# Backplane.net
KiCad netlist of a schematic drawn in EAGLE
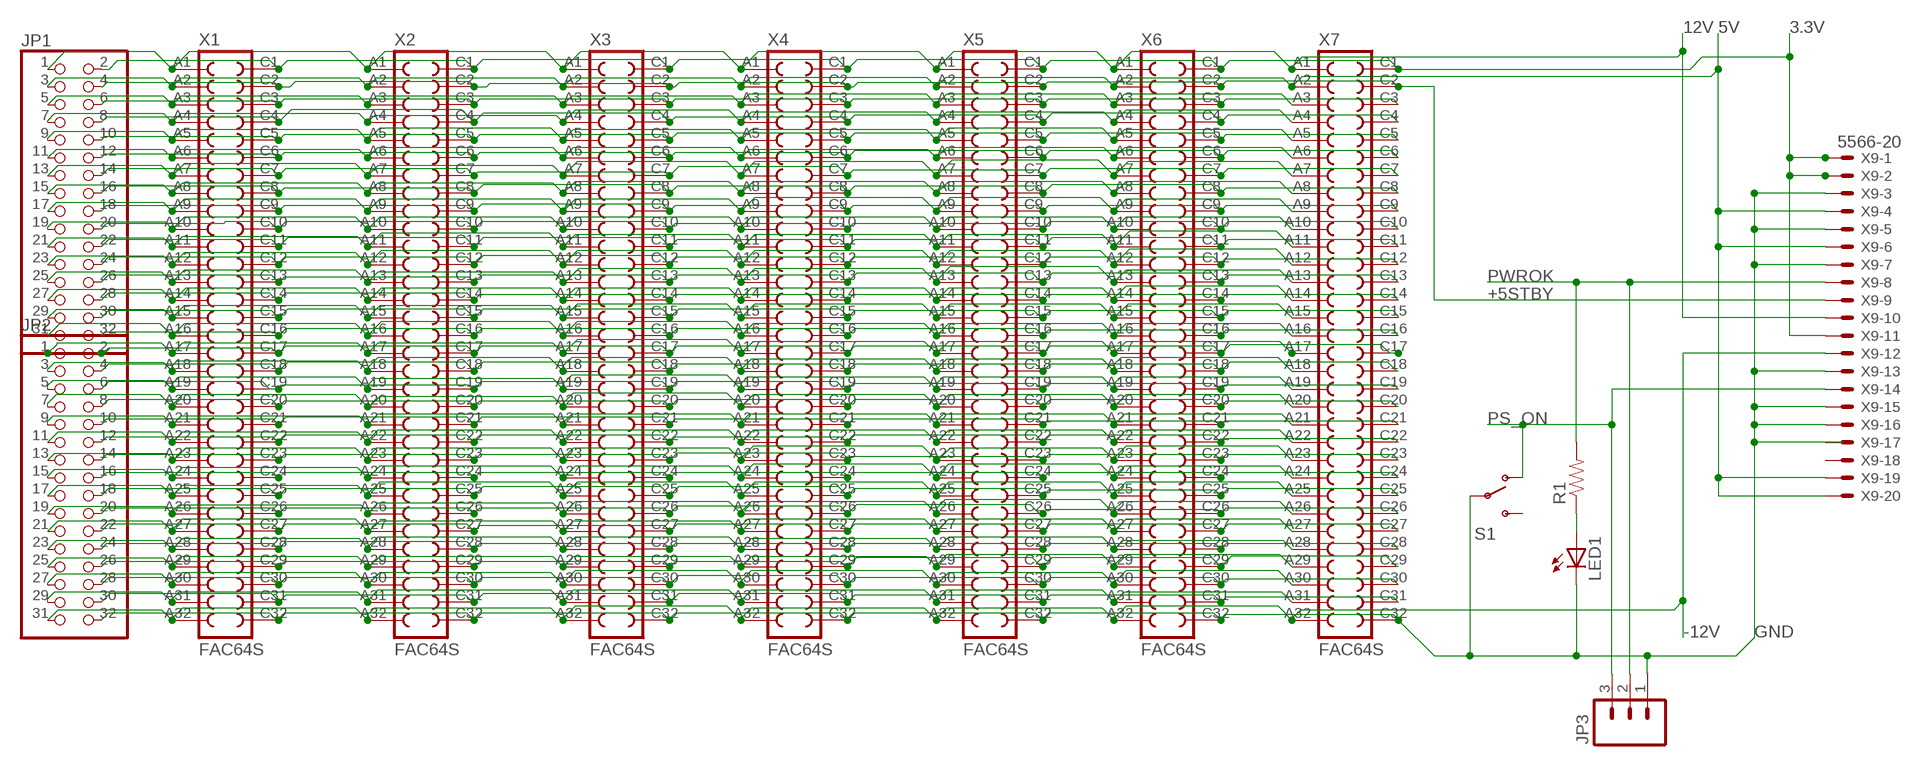
[diagram p0: schematic, sheet 1]

(export (version "E")
  (design (tool "Eeschema 10.0.6"))
  (components
    (comp (ref "JP1")
      (value "PINHD-2X16")
      (footprint "eagle-import:2X16")
      (libsource (lib "eagle-import") (part "PINHD-2X16"))
    )
    (comp (ref "JP2")
      (value "PINHD-2X16")
      (footprint "eagle-import:2X16")
      (libsource (lib "eagle-import") (part "PINHD-2X16"))
    )
    (comp (ref "JP3")
      (value "M03LONGPADS")
      (footprint "eagle-import:1X03_LONGPADS")
      (libsource (lib "eagle-import") (part "M03LONGPADS"))
    )
    (comp (ref "LED1")
      (value "LED3MM")
      (footprint "eagle-import:LED3MM")
      (libsource (lib "eagle-import") (part "LED3MM"))
    )
    (comp (ref "R1")
      (value "RESISTORKIT")
      (footprint "eagle-import:AXIAL-0.3-KIT")
      (libsource (lib "eagle-import") (part "RESISTORKIT"))
    )
    (comp (ref "S1")
      (value "SWITCH-SPDTPTH")
      (footprint "eagle-import:SWITCH-SPDT")
      (libsource (lib "eagle-import") (part "SWITCH-SPDTPTH"))
    )
    (comp (ref "X1")
      (value "FAC64S")
      (footprint "eagle-import:FAC64S")
      (libsource (lib "eagle-import") (part "FAC64S"))
    )
    (comp (ref "X2")
      (value "FAC64S")
      (footprint "eagle-import:FAC64S")
      (libsource (lib "eagle-import") (part "FAC64S"))
    )
    (comp (ref "X3")
      (value "FAC64S")
      (footprint "eagle-import:FAC64S")
      (libsource (lib "eagle-import") (part "FAC64S"))
    )
    (comp (ref "X4")
      (value "FAC64S")
      (footprint "eagle-import:FAC64S")
      (libsource (lib "eagle-import") (part "FAC64S"))
    )
    (comp (ref "X5")
      (value "FAC64S")
      (footprint "eagle-import:FAC64S")
      (libsource (lib "eagle-import") (part "FAC64S"))
    )
    (comp (ref "X6")
      (value "FAC64S")
      (footprint "eagle-import:FAC64S")
      (libsource (lib "eagle-import") (part "FAC64S"))
    )
    (comp (ref "X7")
      (value "FAC64S")
      (footprint "eagle-import:FAC64S")
      (libsource (lib "eagle-import") (part "FAC64S"))
    )
    (comp (ref "X9")
      (value "5566-20")
      (footprint "eagle-import:5566-20")
      (libsource (lib "eagle-import") (part "5566-20"))
    )
  )
  (nets
    (net (code "1") (name "/+5STBY") (class "Default")
      (node (ref "JP1") (pin "4") (pinfunction "4_4") (pintype "passive"))
      (node (ref "X1") (pin "C2") (pinfunction "C2_C2") (pintype "passive"))
      (node (ref "X2") (pin "C2") (pinfunction "C2_C2") (pintype "passive"))
      (node (ref "X3") (pin "C2") (pinfunction "C2_C2") (pintype "passive"))
      (node (ref "X4") (pin "C2") (pinfunction "C2_C2") (pintype "passive"))
      (node (ref "X5") (pin "C2") (pinfunction "C2_C2") (pintype "passive"))
      (node (ref "X6") (pin "C2") (pinfunction "C2_C2") (pintype "passive"))
      (node (ref "X7") (pin "C2") (pinfunction "C2_C2") (pintype "passive"))
      (node (ref "X9") (pin "9") (pinfunction "S_9") (pintype "passive"))
    )
    (net (code "2") (name "/-12V") (class "Default")
      (node (ref "JP2") (pin "31") (pinfunction "31_31") (pintype "passive"))
      (node (ref "X1") (pin "A32") (pinfunction "A32_A32") (pintype "passive"))
      (node (ref "X2") (pin "A32") (pinfunction "A32_A32") (pintype "passive"))
      (node (ref "X3") (pin "A32") (pinfunction "A32_A32") (pintype "passive"))
      (node (ref "X4") (pin "A32") (pinfunction "A32_A32") (pintype "passive"))
      (node (ref "X5") (pin "A32") (pinfunction "A32_A32") (pintype "passive"))
      (node (ref "X6") (pin "A32") (pinfunction "A32_A32") (pintype "passive"))
      (node (ref "X7") (pin "A32") (pinfunction "A32_A32") (pintype "passive"))
      (node (ref "X9") (pin "12") (pinfunction "S_12") (pintype "passive"))
    )
    (net (code "3") (name "/3.3V") (class "Default")
      (node (ref "JP1") (pin "2") (pinfunction "2_2") (pintype "passive"))
      (node (ref "X1") (pin "C1") (pinfunction "C1_C1") (pintype "passive"))
      (node (ref "X2") (pin "C1") (pinfunction "C1_C1") (pintype "passive"))
      (node (ref "X3") (pin "C1") (pinfunction "C1_C1") (pintype "passive"))
      (node (ref "X4") (pin "C1") (pinfunction "C1_C1") (pintype "passive"))
      (node (ref "X5") (pin "C1") (pinfunction "C1_C1") (pintype "passive"))
      (node (ref "X6") (pin "C1") (pinfunction "C1_C1") (pintype "passive"))
      (node (ref "X7") (pin "C1") (pinfunction "C1_C1") (pintype "passive"))
      (node (ref "X9") (pin "1") (pinfunction "S_1") (pintype "passive"))
      (node (ref "X9") (pin "11") (pinfunction "S_11") (pintype "passive"))
      (node (ref "X9") (pin "2") (pinfunction "S_2") (pintype "passive"))
    )
    (net (code "4") (name "/5V") (class "Default")
      (node (ref "JP1") (pin "3") (pinfunction "3_3") (pintype "passive"))
      (node (ref "X1") (pin "A2") (pinfunction "A2_A2") (pintype "passive"))
      (node (ref "X2") (pin "A2") (pinfunction "A2_A2") (pintype "passive"))
      (node (ref "X3") (pin "A2") (pinfunction "A2_A2") (pintype "passive"))
      (node (ref "X4") (pin "A2") (pinfunction "A2_A2") (pintype "passive"))
      (node (ref "X5") (pin "A2") (pinfunction "A2_A2") (pintype "passive"))
      (node (ref "X6") (pin "A2") (pinfunction "A2_A2") (pintype "passive"))
      (node (ref "X7") (pin "A2") (pinfunction "A2_A2") (pintype "passive"))
      (node (ref "X9") (pin "19") (pinfunction "S_19") (pintype "passive"))
      (node (ref "X9") (pin "20") (pinfunction "S_20") (pintype "passive"))
      (node (ref "X9") (pin "4") (pinfunction "S_4") (pintype "passive"))
      (node (ref "X9") (pin "6") (pinfunction "S_6") (pintype "passive"))
    )
    (net (code "5") (name "/12V") (class "Default")
      (node (ref "JP1") (pin "1") (pinfunction "1_1") (pintype "passive"))
      (node (ref "X1") (pin "A1") (pinfunction "A1_A1") (pintype "passive"))
      (node (ref "X2") (pin "A1") (pinfunction "A1_A1") (pintype "passive"))
      (node (ref "X3") (pin "A1") (pinfunction "A1_A1") (pintype "passive"))
      (node (ref "X4") (pin "A1") (pinfunction "A1_A1") (pintype "passive"))
      (node (ref "X5") (pin "A1") (pinfunction "A1_A1") (pintype "passive"))
      (node (ref "X6") (pin "A1") (pinfunction "A1_A1") (pintype "passive"))
      (node (ref "X7") (pin "A1") (pinfunction "A1_A1") (pintype "passive"))
      (node (ref "X9") (pin "10") (pinfunction "S_10") (pintype "passive"))
    )
    (net (code "6") (name "/GND") (class "Default")
      (node (ref "JP2") (pin "32") (pinfunction "32_32") (pintype "passive"))
      (node (ref "JP3") (pin "1") (pinfunction "1_1") (pintype "passive"))
      (node (ref "LED1") (pin "K") (pinfunction "C_K") (pintype "passive"))
      (node (ref "S1") (pin "2") (pinfunction "P_2") (pintype "passive"))
      (node (ref "X1") (pin "C32") (pinfunction "C32_C32") (pintype "passive"))
      (node (ref "X2") (pin "C32") (pinfunction "C32_C32") (pintype "passive"))
      (node (ref "X3") (pin "C32") (pinfunction "C32_C32") (pintype "passive"))
      (node (ref "X4") (pin "C32") (pinfunction "C32_C32") (pintype "passive"))
      (node (ref "X5") (pin "C32") (pinfunction "C32_C32") (pintype "passive"))
      (node (ref "X6") (pin "C32") (pinfunction "C32_C32") (pintype "passive"))
      (node (ref "X7") (pin "C32") (pinfunction "C32_C32") (pintype "passive"))
      (node (ref "X9") (pin "13") (pinfunction "S_13") (pintype "passive"))
      (node (ref "X9") (pin "15") (pinfunction "S_15") (pintype "passive"))
      (node (ref "X9") (pin "16") (pinfunction "S_16") (pintype "passive"))
      (node (ref "X9") (pin "3") (pinfunction "S_3") (pintype "passive"))
      (node (ref "X9") (pin "5") (pinfunction "S_5") (pintype "passive"))
      (node (ref "X9") (pin "7") (pinfunction "S_7") (pintype "passive"))
    )
    (net (code "7") (name "/PS_ON") (class "Default")
      (node (ref "JP3") (pin "3") (pinfunction "3_3") (pintype "passive"))
      (node (ref "S1") (pin "1") (pinfunction "O_1") (pintype "passive"))
      (node (ref "X9") (pin "14") (pinfunction "S_14") (pintype "passive"))
    )
    (net (code "8") (name "/PWROK") (class "Default")
      (node (ref "JP3") (pin "2") (pinfunction "2_2") (pintype "passive"))
      (node (ref "R1") (pin "P$2") (pinfunction "2_P$2") (pintype "passive"))
      (node (ref "X9") (pin "8") (pinfunction "S_8") (pintype "passive"))
    )
    (net (code "9") (name "Net-(JP1-Pad5)") (class "Default")
      (node (ref "JP1") (pin "5") (pinfunction "5_5") (pintype "passive"))
      (node (ref "X1") (pin "A3") (pinfunction "A3_A3") (pintype "passive"))
      (node (ref "X2") (pin "A3") (pinfunction "A3_A3") (pintype "passive"))
      (node (ref "X3") (pin "A3") (pinfunction "A3_A3") (pintype "passive"))
      (node (ref "X4") (pin "A3") (pinfunction "A3_A3") (pintype "passive"))
      (node (ref "X5") (pin "A3") (pinfunction "A3_A3") (pintype "passive"))
      (node (ref "X6") (pin "A3") (pinfunction "A3_A3") (pintype "passive"))
      (node (ref "X7") (pin "A3") (pinfunction "A3_A3") (pintype "passive"))
    )
    (net (code "10") (name "Net-(JP1-Pad6)") (class "Default")
      (node (ref "JP1") (pin "6") (pinfunction "6_6") (pintype "passive"))
      (node (ref "X1") (pin "C3") (pinfunction "C3_C3") (pintype "passive"))
      (node (ref "X2") (pin "C3") (pinfunction "C3_C3") (pintype "passive"))
      (node (ref "X3") (pin "C3") (pinfunction "C3_C3") (pintype "passive"))
      (node (ref "X4") (pin "C3") (pinfunction "C3_C3") (pintype "passive"))
      (node (ref "X5") (pin "C3") (pinfunction "C3_C3") (pintype "passive"))
      (node (ref "X6") (pin "C3") (pinfunction "C3_C3") (pintype "passive"))
      (node (ref "X7") (pin "C3") (pinfunction "C3_C3") (pintype "passive"))
    )
    (net (code "11") (name "Net-(JP1-Pad7)") (class "Default")
      (node (ref "JP1") (pin "7") (pinfunction "7_7") (pintype "passive"))
      (node (ref "X1") (pin "A4") (pinfunction "A4_A4") (pintype "passive"))
      (node (ref "X2") (pin "A4") (pinfunction "A4_A4") (pintype "passive"))
      (node (ref "X3") (pin "A4") (pinfunction "A4_A4") (pintype "passive"))
      (node (ref "X4") (pin "A4") (pinfunction "A4_A4") (pintype "passive"))
      (node (ref "X5") (pin "A4") (pinfunction "A4_A4") (pintype "passive"))
      (node (ref "X6") (pin "A4") (pinfunction "A4_A4") (pintype "passive"))
      (node (ref "X7") (pin "A4") (pinfunction "A4_A4") (pintype "passive"))
    )
    (net (code "12") (name "Net-(JP1-Pad8)") (class "Default")
      (node (ref "JP1") (pin "8") (pinfunction "8_8") (pintype "passive"))
      (node (ref "X1") (pin "C4") (pinfunction "C4_C4") (pintype "passive"))
      (node (ref "X2") (pin "C4") (pinfunction "C4_C4") (pintype "passive"))
      (node (ref "X3") (pin "C4") (pinfunction "C4_C4") (pintype "passive"))
      (node (ref "X4") (pin "C4") (pinfunction "C4_C4") (pintype "passive"))
      (node (ref "X5") (pin "C4") (pinfunction "C4_C4") (pintype "passive"))
      (node (ref "X6") (pin "C4") (pinfunction "C4_C4") (pintype "passive"))
      (node (ref "X7") (pin "C4") (pinfunction "C4_C4") (pintype "passive"))
    )
    (net (code "13") (name "Net-(JP1-Pad9)") (class "Default")
      (node (ref "JP1") (pin "9") (pinfunction "9_9") (pintype "passive"))
      (node (ref "X1") (pin "A5") (pinfunction "A5_A5") (pintype "passive"))
      (node (ref "X2") (pin "A5") (pinfunction "A5_A5") (pintype "passive"))
      (node (ref "X3") (pin "A5") (pinfunction "A5_A5") (pintype "passive"))
      (node (ref "X4") (pin "A5") (pinfunction "A5_A5") (pintype "passive"))
      (node (ref "X5") (pin "A5") (pinfunction "A5_A5") (pintype "passive"))
      (node (ref "X6") (pin "A5") (pinfunction "A5_A5") (pintype "passive"))
      (node (ref "X7") (pin "A5") (pinfunction "A5_A5") (pintype "passive"))
    )
    (net (code "14") (name "Net-(JP1-Pad10)") (class "Default")
      (node (ref "JP1") (pin "10") (pinfunction "10_10") (pintype "passive"))
      (node (ref "X1") (pin "C5") (pinfunction "C5_C5") (pintype "passive"))
      (node (ref "X2") (pin "C5") (pinfunction "C5_C5") (pintype "passive"))
      (node (ref "X3") (pin "C5") (pinfunction "C5_C5") (pintype "passive"))
      (node (ref "X4") (pin "C5") (pinfunction "C5_C5") (pintype "passive"))
      (node (ref "X5") (pin "C5") (pinfunction "C5_C5") (pintype "passive"))
      (node (ref "X6") (pin "C5") (pinfunction "C5_C5") (pintype "passive"))
      (node (ref "X7") (pin "C5") (pinfunction "C5_C5") (pintype "passive"))
    )
    (net (code "15") (name "Net-(JP1-Pad11)") (class "Default")
      (node (ref "JP1") (pin "11") (pinfunction "11_11") (pintype "passive"))
      (node (ref "X1") (pin "A6") (pinfunction "A6_A6") (pintype "passive"))
      (node (ref "X2") (pin "A6") (pinfunction "A6_A6") (pintype "passive"))
      (node (ref "X3") (pin "A6") (pinfunction "A6_A6") (pintype "passive"))
      (node (ref "X4") (pin "A6") (pinfunction "A6_A6") (pintype "passive"))
      (node (ref "X5") (pin "A6") (pinfunction "A6_A6") (pintype "passive"))
      (node (ref "X6") (pin "A6") (pinfunction "A6_A6") (pintype "passive"))
      (node (ref "X7") (pin "A6") (pinfunction "A6_A6") (pintype "passive"))
    )
    (net (code "16") (name "Net-(JP1-Pad12)") (class "Default")
      (node (ref "JP1") (pin "12") (pinfunction "12_12") (pintype "passive"))
      (node (ref "X1") (pin "C6") (pinfunction "C6_C6") (pintype "passive"))
      (node (ref "X2") (pin "C6") (pinfunction "C6_C6") (pintype "passive"))
      (node (ref "X3") (pin "C6") (pinfunction "C6_C6") (pintype "passive"))
      (node (ref "X4") (pin "C6") (pinfunction "C6_C6") (pintype "passive"))
      (node (ref "X5") (pin "C6") (pinfunction "C6_C6") (pintype "passive"))
      (node (ref "X6") (pin "C6") (pinfunction "C6_C6") (pintype "passive"))
      (node (ref "X7") (pin "C6") (pinfunction "C6_C6") (pintype "passive"))
    )
    (net (code "17") (name "Net-(JP1-Pad13)") (class "Default")
      (node (ref "JP1") (pin "13") (pinfunction "13_13") (pintype "passive"))
      (node (ref "X1") (pin "A7") (pinfunction "A7_A7") (pintype "passive"))
      (node (ref "X2") (pin "A7") (pinfunction "A7_A7") (pintype "passive"))
      (node (ref "X3") (pin "A7") (pinfunction "A7_A7") (pintype "passive"))
      (node (ref "X4") (pin "A7") (pinfunction "A7_A7") (pintype "passive"))
      (node (ref "X5") (pin "A7") (pinfunction "A7_A7") (pintype "passive"))
      (node (ref "X6") (pin "A7") (pinfunction "A7_A7") (pintype "passive"))
      (node (ref "X7") (pin "A7") (pinfunction "A7_A7") (pintype "passive"))
    )
    (net (code "18") (name "Net-(JP1-Pad14)") (class "Default")
      (node (ref "JP1") (pin "14") (pinfunction "14_14") (pintype "passive"))
      (node (ref "X1") (pin "C7") (pinfunction "C7_C7") (pintype "passive"))
      (node (ref "X2") (pin "C7") (pinfunction "C7_C7") (pintype "passive"))
      (node (ref "X3") (pin "C7") (pinfunction "C7_C7") (pintype "passive"))
      (node (ref "X4") (pin "C7") (pinfunction "C7_C7") (pintype "passive"))
      (node (ref "X5") (pin "C7") (pinfunction "C7_C7") (pintype "passive"))
      (node (ref "X6") (pin "C7") (pinfunction "C7_C7") (pintype "passive"))
      (node (ref "X7") (pin "C7") (pinfunction "C7_C7") (pintype "passive"))
    )
    (net (code "19") (name "Net-(JP1-Pad15)") (class "Default")
      (node (ref "JP1") (pin "15") (pinfunction "15_15") (pintype "passive"))
      (node (ref "X1") (pin "A8") (pinfunction "A8_A8") (pintype "passive"))
      (node (ref "X2") (pin "A8") (pinfunction "A8_A8") (pintype "passive"))
      (node (ref "X3") (pin "A8") (pinfunction "A8_A8") (pintype "passive"))
      (node (ref "X4") (pin "A8") (pinfunction "A8_A8") (pintype "passive"))
      (node (ref "X5") (pin "A8") (pinfunction "A8_A8") (pintype "passive"))
      (node (ref "X6") (pin "A8") (pinfunction "A8_A8") (pintype "passive"))
      (node (ref "X7") (pin "A8") (pinfunction "A8_A8") (pintype "passive"))
    )
    (net (code "20") (name "Net-(JP1-Pad16)") (class "Default")
      (node (ref "JP1") (pin "16") (pinfunction "16_16") (pintype "passive"))
      (node (ref "X1") (pin "C8") (pinfunction "C8_C8") (pintype "passive"))
      (node (ref "X2") (pin "C8") (pinfunction "C8_C8") (pintype "passive"))
      (node (ref "X3") (pin "C8") (pinfunction "C8_C8") (pintype "passive"))
      (node (ref "X4") (pin "C8") (pinfunction "C8_C8") (pintype "passive"))
      (node (ref "X5") (pin "C8") (pinfunction "C8_C8") (pintype "passive"))
      (node (ref "X6") (pin "C8") (pinfunction "C8_C8") (pintype "passive"))
      (node (ref "X7") (pin "C8") (pinfunction "C8_C8") (pintype "passive"))
    )
    (net (code "21") (name "Net-(JP1-Pad17)") (class "Default")
      (node (ref "JP1") (pin "17") (pinfunction "17_17") (pintype "passive"))
      (node (ref "X1") (pin "A9") (pinfunction "A9_A9") (pintype "passive"))
      (node (ref "X2") (pin "A9") (pinfunction "A9_A9") (pintype "passive"))
      (node (ref "X3") (pin "A9") (pinfunction "A9_A9") (pintype "passive"))
      (node (ref "X4") (pin "A9") (pinfunction "A9_A9") (pintype "passive"))
      (node (ref "X5") (pin "A9") (pinfunction "A9_A9") (pintype "passive"))
      (node (ref "X6") (pin "A9") (pinfunction "A9_A9") (pintype "passive"))
      (node (ref "X7") (pin "A9") (pinfunction "A9_A9") (pintype "passive"))
    )
    (net (code "22") (name "Net-(JP1-Pad18)") (class "Default")
      (node (ref "JP1") (pin "18") (pinfunction "18_18") (pintype "passive"))
      (node (ref "X1") (pin "C9") (pinfunction "C9_C9") (pintype "passive"))
      (node (ref "X2") (pin "C9") (pinfunction "C9_C9") (pintype "passive"))
      (node (ref "X3") (pin "C9") (pinfunction "C9_C9") (pintype "passive"))
      (node (ref "X4") (pin "C9") (pinfunction "C9_C9") (pintype "passive"))
      (node (ref "X5") (pin "C9") (pinfunction "C9_C9") (pintype "passive"))
      (node (ref "X6") (pin "C9") (pinfunction "C9_C9") (pintype "passive"))
      (node (ref "X7") (pin "C9") (pinfunction "C9_C9") (pintype "passive"))
    )
    (net (code "23") (name "Net-(JP1-Pad19)") (class "Default")
      (node (ref "JP1") (pin "19") (pinfunction "19_19") (pintype "passive"))
      (node (ref "X1") (pin "A10") (pinfunction "A10_A10") (pintype "passive"))
      (node (ref "X2") (pin "A10") (pinfunction "A10_A10") (pintype "passive"))
      (node (ref "X3") (pin "A10") (pinfunction "A10_A10") (pintype "passive"))
      (node (ref "X4") (pin "A10") (pinfunction "A10_A10") (pintype "passive"))
      (node (ref "X5") (pin "A10") (pinfunction "A10_A10") (pintype "passive"))
      (node (ref "X6") (pin "A10") (pinfunction "A10_A10") (pintype "passive"))
      (node (ref "X7") (pin "A10") (pinfunction "A10_A10") (pintype "passive"))
    )
    (net (code "24") (name "Net-(JP1-Pad20)") (class "Default")
      (node (ref "JP1") (pin "20") (pinfunction "20_20") (pintype "passive"))
      (node (ref "X1") (pin "C10") (pinfunction "C10_C10") (pintype "passive"))
      (node (ref "X2") (pin "C10") (pinfunction "C10_C10") (pintype "passive"))
      (node (ref "X3") (pin "C10") (pinfunction "C10_C10") (pintype "passive"))
      (node (ref "X4") (pin "C10") (pinfunction "C10_C10") (pintype "passive"))
      (node (ref "X5") (pin "C10") (pinfunction "C10_C10") (pintype "passive"))
      (node (ref "X6") (pin "C10") (pinfunction "C10_C10") (pintype "passive"))
      (node (ref "X7") (pin "C10") (pinfunction "C10_C10") (pintype "passive"))
    )
    (net (code "25") (name "Net-(JP1-Pad21)") (class "Default")
      (node (ref "JP1") (pin "21") (pinfunction "21_21") (pintype "passive"))
      (node (ref "X1") (pin "A11") (pinfunction "A11_A11") (pintype "passive"))
      (node (ref "X2") (pin "A11") (pinfunction "A11_A11") (pintype "passive"))
      (node (ref "X3") (pin "A11") (pinfunction "A11_A11") (pintype "passive"))
      (node (ref "X4") (pin "A11") (pinfunction "A11_A11") (pintype "passive"))
      (node (ref "X5") (pin "A11") (pinfunction "A11_A11") (pintype "passive"))
      (node (ref "X6") (pin "A11") (pinfunction "A11_A11") (pintype "passive"))
      (node (ref "X7") (pin "A11") (pinfunction "A11_A11") (pintype "passive"))
    )
    (net (code "26") (name "Net-(JP1-Pad22)") (class "Default")
      (node (ref "JP1") (pin "22") (pinfunction "22_22") (pintype "passive"))
      (node (ref "X1") (pin "C11") (pinfunction "C11_C11") (pintype "passive"))
      (node (ref "X2") (pin "C11") (pinfunction "C11_C11") (pintype "passive"))
      (node (ref "X3") (pin "C11") (pinfunction "C11_C11") (pintype "passive"))
      (node (ref "X4") (pin "C11") (pinfunction "C11_C11") (pintype "passive"))
      (node (ref "X5") (pin "C11") (pinfunction "C11_C11") (pintype "passive"))
      (node (ref "X6") (pin "C11") (pinfunction "C11_C11") (pintype "passive"))
      (node (ref "X7") (pin "C11") (pinfunction "C11_C11") (pintype "passive"))
    )
    (net (code "27") (name "Net-(JP1-Pad23)") (class "Default")
      (node (ref "JP1") (pin "23") (pinfunction "23_23") (pintype "passive"))
      (node (ref "X1") (pin "A12") (pinfunction "A12_A12") (pintype "passive"))
      (node (ref "X2") (pin "A12") (pinfunction "A12_A12") (pintype "passive"))
      (node (ref "X3") (pin "A12") (pinfunction "A12_A12") (pintype "passive"))
      (node (ref "X4") (pin "A12") (pinfunction "A12_A12") (pintype "passive"))
      (node (ref "X5") (pin "A12") (pinfunction "A12_A12") (pintype "passive"))
      (node (ref "X6") (pin "A12") (pinfunction "A12_A12") (pintype "passive"))
      (node (ref "X7") (pin "A12") (pinfunction "A12_A12") (pintype "passive"))
    )
    (net (code "28") (name "Net-(JP1-Pad24)") (class "Default")
      (node (ref "JP1") (pin "24") (pinfunction "24_24") (pintype "passive"))
      (node (ref "X1") (pin "C12") (pinfunction "C12_C12") (pintype "passive"))
      (node (ref "X2") (pin "C12") (pinfunction "C12_C12") (pintype "passive"))
      (node (ref "X3") (pin "C12") (pinfunction "C12_C12") (pintype "passive"))
      (node (ref "X4") (pin "C12") (pinfunction "C12_C12") (pintype "passive"))
      (node (ref "X5") (pin "C12") (pinfunction "C12_C12") (pintype "passive"))
      (node (ref "X6") (pin "C12") (pinfunction "C12_C12") (pintype "passive"))
      (node (ref "X7") (pin "C12") (pinfunction "C12_C12") (pintype "passive"))
    )
    (net (code "29") (name "Net-(JP1-Pad25)") (class "Default")
      (node (ref "JP1") (pin "25") (pinfunction "25_25") (pintype "passive"))
      (node (ref "X1") (pin "A13") (pinfunction "A13_A13") (pintype "passive"))
      (node (ref "X2") (pin "A13") (pinfunction "A13_A13") (pintype "passive"))
      (node (ref "X3") (pin "A13") (pinfunction "A13_A13") (pintype "passive"))
      (node (ref "X4") (pin "A13") (pinfunction "A13_A13") (pintype "passive"))
      (node (ref "X5") (pin "A13") (pinfunction "A13_A13") (pintype "passive"))
      (node (ref "X6") (pin "A13") (pinfunction "A13_A13") (pintype "passive"))
      (node (ref "X7") (pin "A13") (pinfunction "A13_A13") (pintype "passive"))
    )
    (net (code "30") (name "Net-(JP1-Pad26)") (class "Default")
      (node (ref "JP1") (pin "26") (pinfunction "26_26") (pintype "passive"))
      (node (ref "X1") (pin "C13") (pinfunction "C13_C13") (pintype "passive"))
      (node (ref "X2") (pin "C13") (pinfunction "C13_C13") (pintype "passive"))
      (node (ref "X3") (pin "C13") (pinfunction "C13_C13") (pintype "passive"))
      (node (ref "X4") (pin "C13") (pinfunction "C13_C13") (pintype "passive"))
      (node (ref "X5") (pin "C13") (pinfunction "C13_C13") (pintype "passive"))
      (node (ref "X6") (pin "C13") (pinfunction "C13_C13") (pintype "passive"))
      (node (ref "X7") (pin "C13") (pinfunction "C13_C13") (pintype "passive"))
    )
    (net (code "31") (name "Net-(JP1-Pad27)") (class "Default")
      (node (ref "JP1") (pin "27") (pinfunction "27_27") (pintype "passive"))
      (node (ref "X1") (pin "A14") (pinfunction "A14_A14") (pintype "passive"))
      (node (ref "X2") (pin "A14") (pinfunction "A14_A14") (pintype "passive"))
      (node (ref "X3") (pin "A14") (pinfunction "A14_A14") (pintype "passive"))
      (node (ref "X4") (pin "A14") (pinfunction "A14_A14") (pintype "passive"))
      (node (ref "X5") (pin "A14") (pinfunction "A14_A14") (pintype "passive"))
      (node (ref "X6") (pin "A14") (pinfunction "A14_A14") (pintype "passive"))
      (node (ref "X7") (pin "A14") (pinfunction "A14_A14") (pintype "passive"))
    )
    (net (code "32") (name "Net-(JP1-Pad28)") (class "Default")
      (node (ref "JP1") (pin "28") (pinfunction "28_28") (pintype "passive"))
      (node (ref "X1") (pin "C14") (pinfunction "C14_C14") (pintype "passive"))
      (node (ref "X2") (pin "C14") (pinfunction "C14_C14") (pintype "passive"))
      (node (ref "X3") (pin "C14") (pinfunction "C14_C14") (pintype "passive"))
      (node (ref "X4") (pin "C14") (pinfunction "C14_C14") (pintype "passive"))
      (node (ref "X5") (pin "C14") (pinfunction "C14_C14") (pintype "passive"))
      (node (ref "X6") (pin "C14") (pinfunction "C14_C14") (pintype "passive"))
      (node (ref "X7") (pin "C14") (pinfunction "C14_C14") (pintype "passive"))
    )
    (net (code "33") (name "Net-(JP1-Pad29)") (class "Default")
      (node (ref "JP1") (pin "29") (pinfunction "29_29") (pintype "passive"))
      (node (ref "X1") (pin "A15") (pinfunction "A15_A15") (pintype "passive"))
      (node (ref "X2") (pin "A15") (pinfunction "A15_A15") (pintype "passive"))
      (node (ref "X3") (pin "A15") (pinfunction "A15_A15") (pintype "passive"))
      (node (ref "X4") (pin "A15") (pinfunction "A15_A15") (pintype "passive"))
      (node (ref "X5") (pin "A15") (pinfunction "A15_A15") (pintype "passive"))
      (node (ref "X6") (pin "A15") (pinfunction "A15_A15") (pintype "passive"))
      (node (ref "X7") (pin "A15") (pinfunction "A15_A15") (pintype "passive"))
    )
    (net (code "34") (name "Net-(JP1-Pad30)") (class "Default")
      (node (ref "JP1") (pin "30") (pinfunction "30_30") (pintype "passive"))
      (node (ref "X1") (pin "C15") (pinfunction "C15_C15") (pintype "passive"))
      (node (ref "X2") (pin "C15") (pinfunction "C15_C15") (pintype "passive"))
      (node (ref "X3") (pin "C15") (pinfunction "C15_C15") (pintype "passive"))
      (node (ref "X4") (pin "C15") (pinfunction "C15_C15") (pintype "passive"))
      (node (ref "X5") (pin "C15") (pinfunction "C15_C15") (pintype "passive"))
      (node (ref "X6") (pin "C15") (pinfunction "C15_C15") (pintype "passive"))
      (node (ref "X7") (pin "C15") (pinfunction "C15_C15") (pintype "passive"))
    )
    (net (code "35") (name "Net-(JP1-Pad31)") (class "Default")
      (node (ref "JP1") (pin "31") (pinfunction "31_31") (pintype "passive"))
      (node (ref "X1") (pin "A16") (pinfunction "A16_A16") (pintype "passive"))
      (node (ref "X2") (pin "A16") (pinfunction "A16_A16") (pintype "passive"))
      (node (ref "X3") (pin "A16") (pinfunction "A16_A16") (pintype "passive"))
      (node (ref "X4") (pin "A16") (pinfunction "A16_A16") (pintype "passive"))
      (node (ref "X5") (pin "A16") (pinfunction "A16_A16") (pintype "passive"))
      (node (ref "X6") (pin "A16") (pinfunction "A16_A16") (pintype "passive"))
      (node (ref "X7") (pin "A16") (pinfunction "A16_A16") (pintype "passive"))
    )
    (net (code "36") (name "Net-(JP1-Pad32)") (class "Default")
      (node (ref "JP1") (pin "32") (pinfunction "32_32") (pintype "passive"))
      (node (ref "X1") (pin "C16") (pinfunction "C16_C16") (pintype "passive"))
      (node (ref "X2") (pin "C16") (pinfunction "C16_C16") (pintype "passive"))
      (node (ref "X3") (pin "C16") (pinfunction "C16_C16") (pintype "passive"))
      (node (ref "X4") (pin "C16") (pinfunction "C16_C16") (pintype "passive"))
      (node (ref "X5") (pin "C16") (pinfunction "C16_C16") (pintype "passive"))
      (node (ref "X6") (pin "C16") (pinfunction "C16_C16") (pintype "passive"))
      (node (ref "X7") (pin "C16") (pinfunction "C16_C16") (pintype "passive"))
    )
    (net (code "37") (name "Net-(JP2-Pad1)") (class "Default")
      (node (ref "JP2") (pin "1") (pinfunction "1_1") (pintype "passive"))
      (node (ref "X1") (pin "A17") (pinfunction "A17_A17") (pintype "passive"))
      (node (ref "X2") (pin "A17") (pinfunction "A17_A17") (pintype "passive"))
      (node (ref "X3") (pin "A17") (pinfunction "A17_A17") (pintype "passive"))
      (node (ref "X4") (pin "A17") (pinfunction "A17_A17") (pintype "passive"))
      (node (ref "X5") (pin "A17") (pinfunction "A17_A17") (pintype "passive"))
      (node (ref "X6") (pin "A17") (pinfunction "A17_A17") (pintype "passive"))
      (node (ref "X7") (pin "A17") (pinfunction "A17_A17") (pintype "passive"))
    )
    (net (code "38") (name "Net-(JP2-Pad2)") (class "Default")
      (node (ref "JP2") (pin "2") (pinfunction "2_2") (pintype "passive"))
      (node (ref "X1") (pin "C17") (pinfunction "C17_C17") (pintype "passive"))
      (node (ref "X2") (pin "C17") (pinfunction "C17_C17") (pintype "passive"))
      (node (ref "X3") (pin "C17") (pinfunction "C17_C17") (pintype "passive"))
      (node (ref "X4") (pin "C17") (pinfunction "C17_C17") (pintype "passive"))
      (node (ref "X5") (pin "C17") (pinfunction "C17_C17") (pintype "passive"))
      (node (ref "X6") (pin "C17") (pinfunction "C17_C17") (pintype "passive"))
      (node (ref "X7") (pin "C17") (pinfunction "C17_C17") (pintype "passive"))
    )
    (net (code "39") (name "Net-(JP2-Pad3)") (class "Default")
      (node (ref "JP2") (pin "3") (pinfunction "3_3") (pintype "passive"))
      (node (ref "X1") (pin "A18") (pinfunction "A18_A18") (pintype "passive"))
      (node (ref "X2") (pin "A18") (pinfunction "A18_A18") (pintype "passive"))
      (node (ref "X3") (pin "A18") (pinfunction "A18_A18") (pintype "passive"))
      (node (ref "X4") (pin "A18") (pinfunction "A18_A18") (pintype "passive"))
      (node (ref "X5") (pin "A18") (pinfunction "A18_A18") (pintype "passive"))
      (node (ref "X6") (pin "A18") (pinfunction "A18_A18") (pintype "passive"))
      (node (ref "X7") (pin "A18") (pinfunction "A18_A18") (pintype "passive"))
    )
    (net (code "40") (name "Net-(JP2-Pad4)") (class "Default")
      (node (ref "JP2") (pin "4") (pinfunction "4_4") (pintype "passive"))
      (node (ref "X1") (pin "C18") (pinfunction "C18_C18") (pintype "passive"))
      (node (ref "X2") (pin "C18") (pinfunction "C18_C18") (pintype "passive"))
      (node (ref "X3") (pin "C18") (pinfunction "C18_C18") (pintype "passive"))
      (node (ref "X4") (pin "C18") (pinfunction "C18_C18") (pintype "passive"))
      (node (ref "X5") (pin "C18") (pinfunction "C18_C18") (pintype "passive"))
      (node (ref "X6") (pin "C18") (pinfunction "C18_C18") (pintype "passive"))
      (node (ref "X7") (pin "C18") (pinfunction "C18_C18") (pintype "passive"))
    )
    (net (code "41") (name "Net-(JP2-Pad5)") (class "Default")
      (node (ref "JP2") (pin "5") (pinfunction "5_5") (pintype "passive"))
      (node (ref "X1") (pin "A19") (pinfunction "A19_A19") (pintype "passive"))
      (node (ref "X2") (pin "A19") (pinfunction "A19_A19") (pintype "passive"))
      (node (ref "X3") (pin "A19") (pinfunction "A19_A19") (pintype "passive"))
      (node (ref "X4") (pin "A19") (pinfunction "A19_A19") (pintype "passive"))
      (node (ref "X5") (pin "A19") (pinfunction "A19_A19") (pintype "passive"))
      (node (ref "X6") (pin "A19") (pinfunction "A19_A19") (pintype "passive"))
      (node (ref "X7") (pin "A19") (pinfunction "A19_A19") (pintype "passive"))
    )
    (net (code "42") (name "Net-(JP2-Pad6)") (class "Default")
      (node (ref "JP2") (pin "6") (pinfunction "6_6") (pintype "passive"))
      (node (ref "X1") (pin "C19") (pinfunction "C19_C19") (pintype "passive"))
      (node (ref "X2") (pin "C19") (pinfunction "C19_C19") (pintype "passive"))
      (node (ref "X3") (pin "C19") (pinfunction "C19_C19") (pintype "passive"))
      (node (ref "X4") (pin "C19") (pinfunction "C19_C19") (pintype "passive"))
      (node (ref "X5") (pin "C19") (pinfunction "C19_C19") (pintype "passive"))
      (node (ref "X6") (pin "C19") (pinfunction "C19_C19") (pintype "passive"))
      (node (ref "X7") (pin "C19") (pinfunction "C19_C19") (pintype "passive"))
    )
    (net (code "43") (name "Net-(JP2-Pad7)") (class "Default")
      (node (ref "JP2") (pin "7") (pinfunction "7_7") (pintype "passive"))
      (node (ref "X1") (pin "A20") (pinfunction "A20_A20") (pintype "passive"))
      (node (ref "X2") (pin "A20") (pinfunction "A20_A20") (pintype "passive"))
      (node (ref "X3") (pin "A20") (pinfunction "A20_A20") (pintype "passive"))
      (node (ref "X4") (pin "A20") (pinfunction "A20_A20") (pintype "passive"))
      (node (ref "X5") (pin "A20") (pinfunction "A20_A20") (pintype "passive"))
      (node (ref "X6") (pin "A20") (pinfunction "A20_A20") (pintype "passive"))
      (node (ref "X7") (pin "A20") (pinfunction "A20_A20") (pintype "passive"))
    )
    (net (code "44") (name "Net-(JP2-Pad8)") (class "Default")
      (node (ref "JP2") (pin "8") (pinfunction "8_8") (pintype "passive"))
      (node (ref "X1") (pin "C20") (pinfunction "C20_C20") (pintype "passive"))
      (node (ref "X2") (pin "C20") (pinfunction "C20_C20") (pintype "passive"))
      (node (ref "X3") (pin "C20") (pinfunction "C20_C20") (pintype "passive"))
      (node (ref "X4") (pin "C20") (pinfunction "C20_C20") (pintype "passive"))
      (node (ref "X5") (pin "C20") (pinfunction "C20_C20") (pintype "passive"))
      (node (ref "X6") (pin "C20") (pinfunction "C20_C20") (pintype "passive"))
      (node (ref "X7") (pin "C20") (pinfunction "C20_C20") (pintype "passive"))
    )
    (net (code "45") (name "Net-(JP2-Pad9)") (class "Default")
      (node (ref "JP2") (pin "9") (pinfunction "9_9") (pintype "passive"))
      (node (ref "X1") (pin "A21") (pinfunction "A21_A21") (pintype "passive"))
      (node (ref "X2") (pin "A21") (pinfunction "A21_A21") (pintype "passive"))
      (node (ref "X3") (pin "A21") (pinfunction "A21_A21") (pintype "passive"))
      (node (ref "X4") (pin "A21") (pinfunction "A21_A21") (pintype "passive"))
      (node (ref "X5") (pin "A21") (pinfunction "A21_A21") (pintype "passive"))
      (node (ref "X6") (pin "A21") (pinfunction "A21_A21") (pintype "passive"))
      (node (ref "X7") (pin "A21") (pinfunction "A21_A21") (pintype "passive"))
    )
    (net (code "46") (name "Net-(JP2-Pad10)") (class "Default")
      (node (ref "JP2") (pin "10") (pinfunction "10_10") (pintype "passive"))
      (node (ref "X1") (pin "C21") (pinfunction "C21_C21") (pintype "passive"))
      (node (ref "X2") (pin "C21") (pinfunction "C21_C21") (pintype "passive"))
      (node (ref "X3") (pin "C21") (pinfunction "C21_C21") (pintype "passive"))
      (node (ref "X4") (pin "C21") (pinfunction "C21_C21") (pintype "passive"))
      (node (ref "X5") (pin "C21") (pinfunction "C21_C21") (pintype "passive"))
      (node (ref "X6") (pin "C21") (pinfunction "C21_C21") (pintype "passive"))
      (node (ref "X7") (pin "C21") (pinfunction "C21_C21") (pintype "passive"))
    )
    (net (code "47") (name "Net-(JP2-Pad11)") (class "Default")
      (node (ref "JP2") (pin "11") (pinfunction "11_11") (pintype "passive"))
      (node (ref "X1") (pin "A22") (pinfunction "A22_A22") (pintype "passive"))
      (node (ref "X2") (pin "A22") (pinfunction "A22_A22") (pintype "passive"))
      (node (ref "X3") (pin "A22") (pinfunction "A22_A22") (pintype "passive"))
      (node (ref "X4") (pin "A22") (pinfunction "A22_A22") (pintype "passive"))
      (node (ref "X5") (pin "A22") (pinfunction "A22_A22") (pintype "passive"))
      (node (ref "X6") (pin "A22") (pinfunction "A22_A22") (pintype "passive"))
      (node (ref "X7") (pin "A22") (pinfunction "A22_A22") (pintype "passive"))
    )
    (net (code "48") (name "Net-(JP2-Pad12)") (class "Default")
      (node (ref "JP2") (pin "12") (pinfunction "12_12") (pintype "passive"))
      (node (ref "X1") (pin "C22") (pinfunction "C22_C22") (pintype "passive"))
      (node (ref "X2") (pin "C22") (pinfunction "C22_C22") (pintype "passive"))
      (node (ref "X3") (pin "C22") (pinfunction "C22_C22") (pintype "passive"))
      (node (ref "X4") (pin "C22") (pinfunction "C22_C22") (pintype "passive"))
      (node (ref "X5") (pin "C22") (pinfunction "C22_C22") (pintype "passive"))
      (node (ref "X6") (pin "C22") (pinfunction "C22_C22") (pintype "passive"))
      (node (ref "X7") (pin "C22") (pinfunction "C22_C22") (pintype "passive"))
    )
    (net (code "49") (name "Net-(JP2-Pad13)") (class "Default")
      (node (ref "JP2") (pin "13") (pinfunction "13_13") (pintype "passive"))
      (node (ref "X1") (pin "A23") (pinfunction "A23_A23") (pintype "passive"))
      (node (ref "X2") (pin "A23") (pinfunction "A23_A23") (pintype "passive"))
      (node (ref "X3") (pin "A23") (pinfunction "A23_A23") (pintype "passive"))
      (node (ref "X4") (pin "A23") (pinfunction "A23_A23") (pintype "passive"))
      (node (ref "X5") (pin "A23") (pinfunction "A23_A23") (pintype "passive"))
      (node (ref "X6") (pin "A23") (pinfunction "A23_A23") (pintype "passive"))
      (node (ref "X7") (pin "A23") (pinfunction "A23_A23") (pintype "passive"))
    )
    (net (code "50") (name "Net-(JP2-Pad14)") (class "Default")
      (node (ref "JP2") (pin "14") (pinfunction "14_14") (pintype "passive"))
      (node (ref "X1") (pin "C23") (pinfunction "C23_C23") (pintype "passive"))
      (node (ref "X2") (pin "C23") (pinfunction "C23_C23") (pintype "passive"))
      (node (ref "X3") (pin "C23") (pinfunction "C23_C23") (pintype "passive"))
      (node (ref "X4") (pin "C23") (pinfunction "C23_C23") (pintype "passive"))
      (node (ref "X5") (pin "C23") (pinfunction "C23_C23") (pintype "passive"))
      (node (ref "X6") (pin "C23") (pinfunction "C23_C23") (pintype "passive"))
      (node (ref "X7") (pin "C23") (pinfunction "C23_C23") (pintype "passive"))
    )
    (net (code "51") (name "Net-(JP2-Pad15)") (class "Default")
      (node (ref "JP2") (pin "15") (pinfunction "15_15") (pintype "passive"))
      (node (ref "X1") (pin "A24") (pinfunction "A24_A24") (pintype "passive"))
      (node (ref "X2") (pin "A24") (pinfunction "A24_A24") (pintype "passive"))
      (node (ref "X3") (pin "A24") (pinfunction "A24_A24") (pintype "passive"))
      (node (ref "X4") (pin "A24") (pinfunction "A24_A24") (pintype "passive"))
      (node (ref "X5") (pin "A24") (pinfunction "A24_A24") (pintype "passive"))
      (node (ref "X6") (pin "A24") (pinfunction "A24_A24") (pintype "passive"))
      (node (ref "X7") (pin "A24") (pinfunction "A24_A24") (pintype "passive"))
    )
    (net (code "52") (name "Net-(JP2-Pad16)") (class "Default")
      (node (ref "JP2") (pin "16") (pinfunction "16_16") (pintype "passive"))
      (node (ref "X1") (pin "C24") (pinfunction "C24_C24") (pintype "passive"))
      (node (ref "X2") (pin "C24") (pinfunction "C24_C24") (pintype "passive"))
      (node (ref "X3") (pin "C24") (pinfunction "C24_C24") (pintype "passive"))
      (node (ref "X4") (pin "C24") (pinfunction "C24_C24") (pintype "passive"))
      (node (ref "X5") (pin "C24") (pinfunction "C24_C24") (pintype "passive"))
      (node (ref "X6") (pin "C24") (pinfunction "C24_C24") (pintype "passive"))
      (node (ref "X7") (pin "C24") (pinfunction "C24_C24") (pintype "passive"))
    )
    (net (code "53") (name "Net-(JP2-Pad17)") (class "Default")
      (node (ref "JP2") (pin "17") (pinfunction "17_17") (pintype "passive"))
      (node (ref "X1") (pin "A25") (pinfunction "A25_A25") (pintype "passive"))
      (node (ref "X2") (pin "A25") (pinfunction "A25_A25") (pintype "passive"))
      (node (ref "X3") (pin "A25") (pinfunction "A25_A25") (pintype "passive"))
      (node (ref "X4") (pin "A25") (pinfunction "A25_A25") (pintype "passive"))
      (node (ref "X5") (pin "A25") (pinfunction "A25_A25") (pintype "passive"))
      (node (ref "X6") (pin "A25") (pinfunction "A25_A25") (pintype "passive"))
      (node (ref "X7") (pin "A25") (pinfunction "A25_A25") (pintype "passive"))
    )
    (net (code "54") (name "Net-(JP2-Pad18)") (class "Default")
      (node (ref "JP2") (pin "18") (pinfunction "18_18") (pintype "passive"))
      (node (ref "X1") (pin "C25") (pinfunction "C25_C25") (pintype "passive"))
      (node (ref "X2") (pin "C25") (pinfunction "C25_C25") (pintype "passive"))
      (node (ref "X3") (pin "C25") (pinfunction "C25_C25") (pintype "passive"))
      (node (ref "X4") (pin "C25") (pinfunction "C25_C25") (pintype "passive"))
      (node (ref "X5") (pin "C25") (pinfunction "C25_C25") (pintype "passive"))
      (node (ref "X6") (pin "C25") (pinfunction "C25_C25") (pintype "passive"))
      (node (ref "X7") (pin "C25") (pinfunction "C25_C25") (pintype "passive"))
    )
    (net (code "55") (name "Net-(JP2-Pad19)") (class "Default")
      (node (ref "JP2") (pin "19") (pinfunction "19_19") (pintype "passive"))
      (node (ref "X1") (pin "A26") (pinfunction "A26_A26") (pintype "passive"))
      (node (ref "X2") (pin "A26") (pinfunction "A26_A26") (pintype "passive"))
      (node (ref "X3") (pin "A26") (pinfunction "A26_A26") (pintype "passive"))
      (node (ref "X4") (pin "A26") (pinfunction "A26_A26") (pintype "passive"))
      (node (ref "X5") (pin "A26") (pinfunction "A26_A26") (pintype "passive"))
      (node (ref "X6") (pin "A26") (pinfunction "A26_A26") (pintype "passive"))
      (node (ref "X7") (pin "A26") (pinfunction "A26_A26") (pintype "passive"))
    )
    (net (code "56") (name "Net-(JP2-Pad20)") (class "Default")
      (node (ref "JP2") (pin "20") (pinfunction "20_20") (pintype "passive"))
      (node (ref "X1") (pin "C26") (pinfunction "C26_C26") (pintype "passive"))
      (node (ref "X2") (pin "C26") (pinfunction "C26_C26") (pintype "passive"))
      (node (ref "X3") (pin "C26") (pinfunction "C26_C26") (pintype "passive"))
      (node (ref "X4") (pin "C26") (pinfunction "C26_C26") (pintype "passive"))
      (node (ref "X5") (pin "C26") (pinfunction "C26_C26") (pintype "passive"))
      (node (ref "X6") (pin "C26") (pinfunction "C26_C26") (pintype "passive"))
      (node (ref "X7") (pin "C26") (pinfunction "C26_C26") (pintype "passive"))
    )
    (net (code "57") (name "Net-(JP2-Pad21)") (class "Default")
      (node (ref "JP2") (pin "21") (pinfunction "21_21") (pintype "passive"))
      (node (ref "X1") (pin "A27") (pinfunction "A27_A27") (pintype "passive"))
      (node (ref "X2") (pin "A27") (pinfunction "A27_A27") (pintype "passive"))
      (node (ref "X3") (pin "A27") (pinfunction "A27_A27") (pintype "passive"))
      (node (ref "X4") (pin "A27") (pinfunction "A27_A27") (pintype "passive"))
      (node (ref "X5") (pin "A27") (pinfunction "A27_A27") (pintype "passive"))
      (node (ref "X6") (pin "A27") (pinfunction "A27_A27") (pintype "passive"))
      (node (ref "X7") (pin "A27") (pinfunction "A27_A27") (pintype "passive"))
    )
    (net (code "58") (name "Net-(JP2-Pad22)") (class "Default")
      (node (ref "JP2") (pin "22") (pinfunction "22_22") (pintype "passive"))
      (node (ref "X1") (pin "C27") (pinfunction "C27_C27") (pintype "passive"))
      (node (ref "X2") (pin "C27") (pinfunction "C27_C27") (pintype "passive"))
      (node (ref "X3") (pin "C27") (pinfunction "C27_C27") (pintype "passive"))
      (node (ref "X4") (pin "C27") (pinfunction "C27_C27") (pintype "passive"))
      (node (ref "X5") (pin "C27") (pinfunction "C27_C27") (pintype "passive"))
      (node (ref "X6") (pin "C27") (pinfunction "C27_C27") (pintype "passive"))
      (node (ref "X7") (pin "C27") (pinfunction "C27_C27") (pintype "passive"))
    )
    (net (code "59") (name "Net-(JP2-Pad23)") (class "Default")
      (node (ref "JP2") (pin "23") (pinfunction "23_23") (pintype "passive"))
      (node (ref "X1") (pin "A28") (pinfunction "A28_A28") (pintype "passive"))
      (node (ref "X2") (pin "A28") (pinfunction "A28_A28") (pintype "passive"))
      (node (ref "X3") (pin "A28") (pinfunction "A28_A28") (pintype "passive"))
      (node (ref "X4") (pin "A28") (pinfunction "A28_A28") (pintype "passive"))
      (node (ref "X5") (pin "A28") (pinfunction "A28_A28") (pintype "passive"))
      (node (ref "X6") (pin "A28") (pinfunction "A28_A28") (pintype "passive"))
      (node (ref "X7") (pin "A28") (pinfunction "A28_A28") (pintype "passive"))
    )
    (net (code "60") (name "Net-(JP2-Pad24)") (class "Default")
      (node (ref "JP2") (pin "24") (pinfunction "24_24") (pintype "passive"))
      (node (ref "X1") (pin "C28") (pinfunction "C28_C28") (pintype "passive"))
      (node (ref "X2") (pin "C28") (pinfunction "C28_C28") (pintype "passive"))
      (node (ref "X3") (pin "C28") (pinfunction "C28_C28") (pintype "passive"))
      (node (ref "X4") (pin "C28") (pinfunction "C28_C28") (pintype "passive"))
      (node (ref "X5") (pin "C28") (pinfunction "C28_C28") (pintype "passive"))
      (node (ref "X6") (pin "C28") (pinfunction "C28_C28") (pintype "passive"))
      (node (ref "X7") (pin "C28") (pinfunction "C28_C28") (pintype "passive"))
    )
    (net (code "61") (name "Net-(JP2-Pad25)") (class "Default")
      (node (ref "JP2") (pin "25") (pinfunction "25_25") (pintype "passive"))
      (node (ref "X1") (pin "A29") (pinfunction "A29_A29") (pintype "passive"))
      (node (ref "X2") (pin "A29") (pinfunction "A29_A29") (pintype "passive"))
      (node (ref "X3") (pin "A29") (pinfunction "A29_A29") (pintype "passive"))
      (node (ref "X4") (pin "A29") (pinfunction "A29_A29") (pintype "passive"))
      (node (ref "X5") (pin "A29") (pinfunction "A29_A29") (pintype "passive"))
      (node (ref "X6") (pin "A29") (pinfunction "A29_A29") (pintype "passive"))
      (node (ref "X7") (pin "A29") (pinfunction "A29_A29") (pintype "passive"))
    )
    (net (code "62") (name "Net-(JP2-Pad26)") (class "Default")
      (node (ref "JP2") (pin "26") (pinfunction "26_26") (pintype "passive"))
      (node (ref "X1") (pin "C29") (pinfunction "C29_C29") (pintype "passive"))
      (node (ref "X2") (pin "C29") (pinfunction "C29_C29") (pintype "passive"))
      (node (ref "X3") (pin "C29") (pinfunction "C29_C29") (pintype "passive"))
      (node (ref "X4") (pin "C29") (pinfunction "C29_C29") (pintype "passive"))
      (node (ref "X5") (pin "C29") (pinfunction "C29_C29") (pintype "passive"))
      (node (ref "X6") (pin "C29") (pinfunction "C29_C29") (pintype "passive"))
      (node (ref "X7") (pin "C29") (pinfunction "C29_C29") (pintype "passive"))
    )
    (net (code "63") (name "Net-(JP2-Pad27)") (class "Default")
      (node (ref "JP2") (pin "27") (pinfunction "27_27") (pintype "passive"))
      (node (ref "X1") (pin "A30") (pinfunction "A30_A30") (pintype "passive"))
      (node (ref "X2") (pin "A30") (pinfunction "A30_A30") (pintype "passive"))
      (node (ref "X3") (pin "A30") (pinfunction "A30_A30") (pintype "passive"))
      (node (ref "X4") (pin "A30") (pinfunction "A30_A30") (pintype "passive"))
      (node (ref "X5") (pin "A30") (pinfunction "A30_A30") (pintype "passive"))
      (node (ref "X6") (pin "A30") (pinfunction "A30_A30") (pintype "passive"))
      (node (ref "X7") (pin "A30") (pinfunction "A30_A30") (pintype "passive"))
    )
    (net (code "64") (name "Net-(JP2-Pad28)") (class "Default")
      (node (ref "JP2") (pin "28") (pinfunction "28_28") (pintype "passive"))
      (node (ref "X1") (pin "C30") (pinfunction "C30_C30") (pintype "passive"))
      (node (ref "X2") (pin "C30") (pinfunction "C30_C30") (pintype "passive"))
      (node (ref "X3") (pin "C30") (pinfunction "C30_C30") (pintype "passive"))
      (node (ref "X4") (pin "C30") (pinfunction "C30_C30") (pintype "passive"))
      (node (ref "X5") (pin "C30") (pinfunction "C30_C30") (pintype "passive"))
      (node (ref "X6") (pin "C30") (pinfunction "C30_C30") (pintype "passive"))
      (node (ref "X7") (pin "C30") (pinfunction "C30_C30") (pintype "passive"))
    )
    (net (code "65") (name "Net-(JP2-Pad29)") (class "Default")
      (node (ref "JP2") (pin "29") (pinfunction "29_29") (pintype "passive"))
      (node (ref "X1") (pin "A31") (pinfunction "A31_A31") (pintype "passive"))
      (node (ref "X2") (pin "A31") (pinfunction "A31_A31") (pintype "passive"))
      (node (ref "X3") (pin "A31") (pinfunction "A31_A31") (pintype "passive"))
      (node (ref "X4") (pin "A31") (pinfunction "A31_A31") (pintype "passive"))
      (node (ref "X5") (pin "A31") (pinfunction "A31_A31") (pintype "passive"))
      (node (ref "X6") (pin "A31") (pinfunction "A31_A31") (pintype "passive"))
      (node (ref "X7") (pin "A31") (pinfunction "A31_A31") (pintype "passive"))
    )
    (net (code "66") (name "Net-(JP2-Pad30)") (class "Default")
      (node (ref "JP2") (pin "30") (pinfunction "30_30") (pintype "passive"))
      (node (ref "X1") (pin "C31") (pinfunction "C31_C31") (pintype "passive"))
      (node (ref "X2") (pin "C31") (pinfunction "C31_C31") (pintype "passive"))
      (node (ref "X3") (pin "C31") (pinfunction "C31_C31") (pintype "passive"))
      (node (ref "X4") (pin "C31") (pinfunction "C31_C31") (pintype "passive"))
      (node (ref "X5") (pin "C31") (pinfunction "C31_C31") (pintype "passive"))
      (node (ref "X6") (pin "C31") (pinfunction "C31_C31") (pintype "passive"))
      (node (ref "X7") (pin "C31") (pinfunction "C31_C31") (pintype "passive"))
    )
    (net (code "67") (name "Net-(R1-1)") (class "Default")
      (node (ref "LED1") (pin "A") (pinfunction "A_A") (pintype "passive"))
      (node (ref "R1") (pin "P$1") (pinfunction "1_P$1") (pintype "passive"))
    )
    (net (code "68") (name "unconnected-(S1-S-Pad3)") (class "Default")
      (node (ref "S1") (pin "3") (pinfunction "S_3") (pintype "passive"))
    )
    (net (code "69") (name "unconnected-(X9I-S-Pad17)") (class "Default")
      (node (ref "X9") (pin "17") (pinfunction "S_17") (pintype "passive"))
    )
    (net (code "70") (name "unconnected-(X9J-S-Pad18)") (class "Default")
      (node (ref "X9") (pin "18") (pinfunction "S_18") (pintype "passive"))
    )
  )
)
